# Half_Bridge.net
KiCad netlist of a schematic drawn in Altium Designer
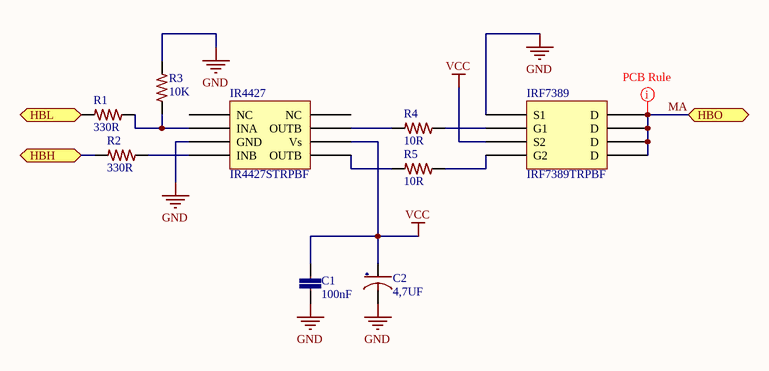
[diagram p0: Half_Bridge.SchDoc]

(export (version "E")
  (design (tool "Eeschema 10.0.6"))
  (components
    (comp (ref "C1")
      (value "100nF")
      (footprint "0402-CAP")
      (description "CAP CER 100PF 50V 1% NP0 0402")
      (fields (field (name "PART NO") "GRM1555C1H101FA01D"))
      (libsource (lib "IMBEL") (part "CAPACITOR"))
    )
    (comp (ref "C2")
      (value "4,7UF")
      (footprint "PCBComponent")
      (description "Tantalum Capacitors - Solid SMD 10uF 35V 10% L ESR")
      (libsource (lib "IMBEL") (part "TPSD106K035R0300-01.A.1"))
    )
    (comp (ref "IR4427")
      (value "IR4427STRPBF")
      (footprint "IR4427-PCB")
      (description "IC DRIVER DUAL LOW SIDE 8-DIP")
      (libsource (lib "Schlib1") (part "IR4427"))
    )
    (comp (ref "IRF7389")
      (value "IRF7389TRPBF")
      (footprint "IRF7389-PCB")
      (description "MOSFET N/P-CH 30V 8-SOIC")
      (libsource (lib "Schlib1") (part "IRF7389"))
    )
    (comp (ref "R1")
      (value "330R")
      (footprint "0402-RES-HD")
      (description "RES 330 OHM 1/10W 1% 0402 SMD")
      (fields (field (name "PART NO") "ERJ-2RKF3300X"))
      (libsource (lib "IMBEL") (part "RESISTOR"))
    )
    (comp (ref "R2")
      (value "330R")
      (footprint "0402-RES-HD")
      (description "RES 330 OHM 1/10W 1% 0402 SMD")
      (fields (field (name "PART NO") "ERJ-2RKF3300X"))
      (libsource (lib "IMBEL") (part "R0402-330R-7"))
    )
    (comp (ref "R3")
      (value "10K")
      (footprint "0402-RES-HD")
      (description "RES 10K OHM 1/10W 1% 0402 SMD")
      (fields (field (name "PART NO") "ERJ-2RKF1002X"))
      (libsource (lib "IMBEL") (part "R0402-10K-10"))
    )
    (comp (ref "R4")
      (value "10R")
      (footprint "0402-RES-HD")
      (description "RES 10 OHM 1/10W 1% 0402 SMD")
      (fields (field (name "PART NO") "ERJ-2RKF10R0X"))
      (libsource (lib "IMBEL") (part "RESISTOR"))
    )
    (comp (ref "R5")
      (value "10R")
      (footprint "0402-RES-HD")
      (description "RES 10 OHM 1/10W 1% 0402 SMD")
      (fields (field (name "PART NO") "ERJ-2RKF10R0X"))
      (libsource (lib "IMBEL") (part "R0402-10R-6"))
    )
  )
  (nets
    (net (code "1") (name "/HBH") (class "Default")
      (node (ref "R2") (pin "1") (pinfunction "1_1") (pintype "passive"))
    )
    (net (code "2") (name "/HBL") (class "Default")
      (node (ref "R1") (pin "1") (pinfunction "1_1") (pintype "passive"))
    )
    (net (code "3") (name "/MA") (class "Default")
      (node (ref "IRF7389") (pin "5") (pinfunction "D_5") (pintype "passive"))
      (node (ref "IRF7389") (pin "6") (pinfunction "D_6") (pintype "passive"))
      (node (ref "IRF7389") (pin "7") (pinfunction "D_7") (pintype "passive"))
      (node (ref "IRF7389") (pin "8") (pinfunction "D_8") (pintype "passive"))
    )
    (net (code "4") (name "GND") (class "Default")
      (node (ref "C1") (pin "2") (pinfunction "2_2") (pintype "passive"))
      (node (ref "C2") (pin "2") (pinfunction "-_2") (pintype "passive"))
      (node (ref "IR4427") (pin "3") (pinfunction "GND_3") (pintype "passive"))
      (node (ref "IRF7389") (pin "1") (pinfunction "S1_1") (pintype "passive"))
      (node (ref "R3") (pin "1") (pinfunction "1_1") (pintype "passive"))
    )
    (net (code "5") (name "Net-(IR4427-INA)") (class "Default")
      (node (ref "IR4427") (pin "2") (pinfunction "INA_2") (pintype "passive"))
      (node (ref "R1") (pin "2") (pinfunction "2_2") (pintype "passive"))
      (node (ref "R3") (pin "2") (pinfunction "2_2") (pintype "passive"))
    )
    (net (code "6") (name "Net-(IR4427-INB)") (class "Default")
      (node (ref "IR4427") (pin "4") (pinfunction "INB_4") (pintype "passive"))
      (node (ref "R2") (pin "2") (pinfunction "2_2") (pintype "passive"))
    )
    (net (code "7") (name "Net-(IR4427-OUTB-Pad5)") (class "Default")
      (node (ref "IR4427") (pin "5") (pinfunction "OUTB_5") (pintype "passive"))
      (node (ref "R5") (pin "1") (pinfunction "1_1") (pintype "passive"))
    )
    (net (code "8") (name "Net-(IR4427-OUTB-Pad7)") (class "Default")
      (node (ref "IR4427") (pin "7") (pinfunction "OUTB_7") (pintype "passive"))
      (node (ref "R4") (pin "1") (pinfunction "1_1") (pintype "passive"))
    )
    (net (code "9") (name "Net-(IRF7389-G1)") (class "Default")
      (node (ref "IRF7389") (pin "2") (pinfunction "G1_2") (pintype "passive"))
      (node (ref "R4") (pin "2") (pinfunction "2_2") (pintype "passive"))
    )
    (net (code "10") (name "Net-(IRF7389-G2)") (class "Default")
      (node (ref "IRF7389") (pin "4") (pinfunction "G2_4") (pintype "passive"))
      (node (ref "R5") (pin "2") (pinfunction "2_2") (pintype "passive"))
    )
    (net (code "11") (name "VCC") (class "Default")
      (node (ref "C1") (pin "1") (pinfunction "1_1") (pintype "passive"))
      (node (ref "C2") (pin "1") (pinfunction "+_1") (pintype "passive"))
      (node (ref "IR4427") (pin "6") (pinfunction "Vs_6") (pintype "passive"))
      (node (ref "IRF7389") (pin "3") (pinfunction "S2_3") (pintype "passive"))
    )
    (net (code "12") (name "unconnected-(IR4427-NC-Pad1)") (class "Default")
      (node (ref "IR4427") (pin "1") (pinfunction "NC_1") (pintype "passive"))
    )
    (net (code "13") (name "unconnected-(IR4427-NC-Pad8)") (class "Default")
      (node (ref "IR4427") (pin "8") (pinfunction "NC_8") (pintype "passive"))
    )
  )
)
